# Blinky.net
KiCad netlist of a schematic drawn in EAGLE
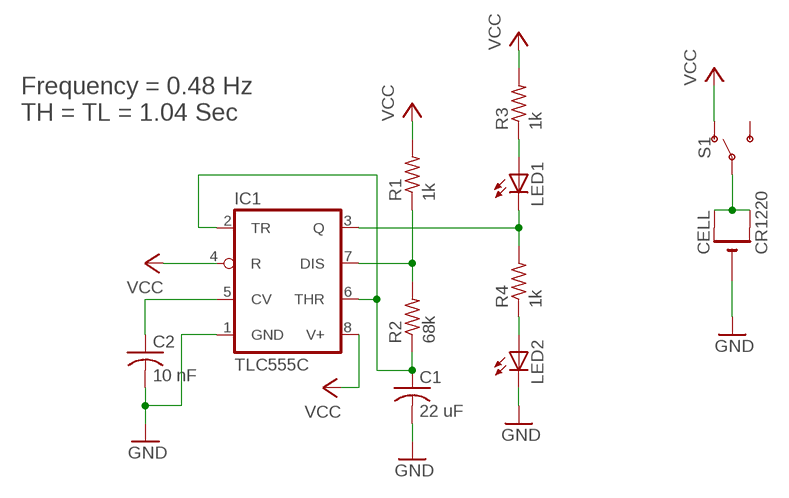
[diagram p0: schematic, sheet 1]

(export (version "E")
  (design (tool "Eeschema 10.0.6"))
  (components
    (comp (ref "C1")
      (value "22 uF")
      (footprint "eagle-import:C1206")
      (libsource (lib "eagle-import") (part "C-USC1206"))
    )
    (comp (ref "C2")
      (value "10 nF")
      (footprint "eagle-import:C1206")
      (libsource (lib "eagle-import") (part "C-USC1206"))
    )
    (comp (ref "CELL")
      (value "CR1220")
      (footprint "eagle-import:CR1220-SMD")
      (libsource (lib "eagle-import") (part "CR1220SMT"))
    )
    (comp (ref "IC1")
      (value "TLC555C")
      (footprint "eagle-import:SO08")
      (libsource (lib "eagle-import") (part "555DLM"))
    )
    (comp (ref "LED1")
      (value "LEDCHIPLED_1206")
      (footprint "eagle-import:CHIPLED_1206")
      (libsource (lib "eagle-import") (part "LEDCHIPLED_1206"))
    )
    (comp (ref "LED2")
      (value "LEDCHIPLED_1206")
      (footprint "eagle-import:CHIPLED_1206")
      (libsource (lib "eagle-import") (part "LEDCHIPLED_1206"))
    )
    (comp (ref "R1")
      (value "1k")
      (footprint "eagle-import:R1206")
      (libsource (lib "eagle-import") (part "R-US_R1206"))
    )
    (comp (ref "R2")
      (value "68k")
      (footprint "eagle-import:R1206")
      (libsource (lib "eagle-import") (part "R-US_R1206"))
    )
    (comp (ref "R3")
      (value "1k")
      (footprint "eagle-import:R1206")
      (libsource (lib "eagle-import") (part "R-US_R1206"))
    )
    (comp (ref "R4")
      (value "1k")
      (footprint "eagle-import:R1206")
      (libsource (lib "eagle-import") (part "R-US_R1206"))
    )
    (comp (ref "S1")
      (value "SWITCH-SPDT-SMD-RIGHT-ANGLE")
      (footprint "eagle-import:SWITCH_SPST_SMD_A")
      (libsource (lib "eagle-import") (part "SWITCH-SPDT-SMD-RIGHT-ANGLE"))
    )
  )
  (nets
    (net (code "1") (name "GND") (class "Default")
      (node (ref "C1") (pin "2") (pinfunction "2_2") (pintype "passive"))
      (node (ref "C2") (pin "2") (pinfunction "2_2") (pintype "passive"))
      (node (ref "CELL") (pin "-") (pinfunction "-_-") (pintype "passive"))
      (node (ref "IC1") (pin "1") (pinfunction "GND_1") (pintype "power_in"))
      (node (ref "LED2") (pin "C") (pinfunction "C_C") (pintype "passive"))
    )
    (net (code "2") (name "Net-(CELL-+)") (class "Default")
      (node (ref "CELL") (pin "+$1") (pinfunction "+_+$1") (pintype "passive"))
      (node (ref "CELL") (pin "+$2") (pinfunction "+1_+$2") (pintype "passive"))
      (node (ref "S1") (pin "2") (pinfunction "P_2") (pintype "passive"))
    )
    (net (code "3") (name "Net-(IC1-CV)") (class "Default")
      (node (ref "C2") (pin "1") (pinfunction "1_1") (pintype "passive"))
      (node (ref "IC1") (pin "5") (pinfunction "CV_5") (pintype "input"))
    )
    (net (code "4") (name "Net-(IC1-DIS)") (class "Default")
      (node (ref "IC1") (pin "7") (pinfunction "DIS_7") (pintype "input"))
      (node (ref "R1") (pin "1") (pinfunction "1_1") (pintype "passive"))
      (node (ref "R2") (pin "2") (pinfunction "2_2") (pintype "passive"))
    )
    (net (code "5") (name "Net-(IC1-Q)") (class "Default")
      (node (ref "IC1") (pin "3") (pinfunction "Q_3") (pintype "output"))
      (node (ref "LED1") (pin "C") (pinfunction "C_C") (pintype "passive"))
      (node (ref "R4") (pin "2") (pinfunction "2_2") (pintype "passive"))
    )
    (net (code "6") (name "Net-(IC1-THR)") (class "Default")
      (node (ref "C1") (pin "1") (pinfunction "1_1") (pintype "passive"))
      (node (ref "IC1") (pin "2") (pinfunction "TR_2") (pintype "input"))
      (node (ref "IC1") (pin "6") (pinfunction "THR_6") (pintype "input"))
      (node (ref "R2") (pin "1") (pinfunction "1_1") (pintype "passive"))
    )
    (net (code "7") (name "Net-(LED1-PadA)") (class "Default")
      (node (ref "LED1") (pin "A") (pinfunction "A_A") (pintype "passive"))
      (node (ref "R3") (pin "1") (pinfunction "1_1") (pintype "passive"))
    )
    (net (code "8") (name "Net-(LED2-PadA)") (class "Default")
      (node (ref "LED2") (pin "A") (pinfunction "A_A") (pintype "passive"))
      (node (ref "R4") (pin "1") (pinfunction "1_1") (pintype "passive"))
    )
    (net (code "9") (name "VCC") (class "Default")
      (node (ref "IC1") (pin "4") (pinfunction "R_4") (pintype "input"))
      (node (ref "IC1") (pin "8") (pinfunction "V+_8") (pintype "power_in"))
      (node (ref "R1") (pin "2") (pinfunction "2_2") (pintype "passive"))
      (node (ref "R3") (pin "2") (pinfunction "2_2") (pintype "passive"))
      (node (ref "S1") (pin "1") (pinfunction "O_1") (pintype "passive"))
    )
    (net (code "10") (name "unconnected-(S1-S-Pad3)") (class "Default")
      (node (ref "S1") (pin "3") (pinfunction "S_3") (pintype "passive"))
    )
  )
)
